# Board_2.net
KiCad netlist of a schematic drawn in EAGLE
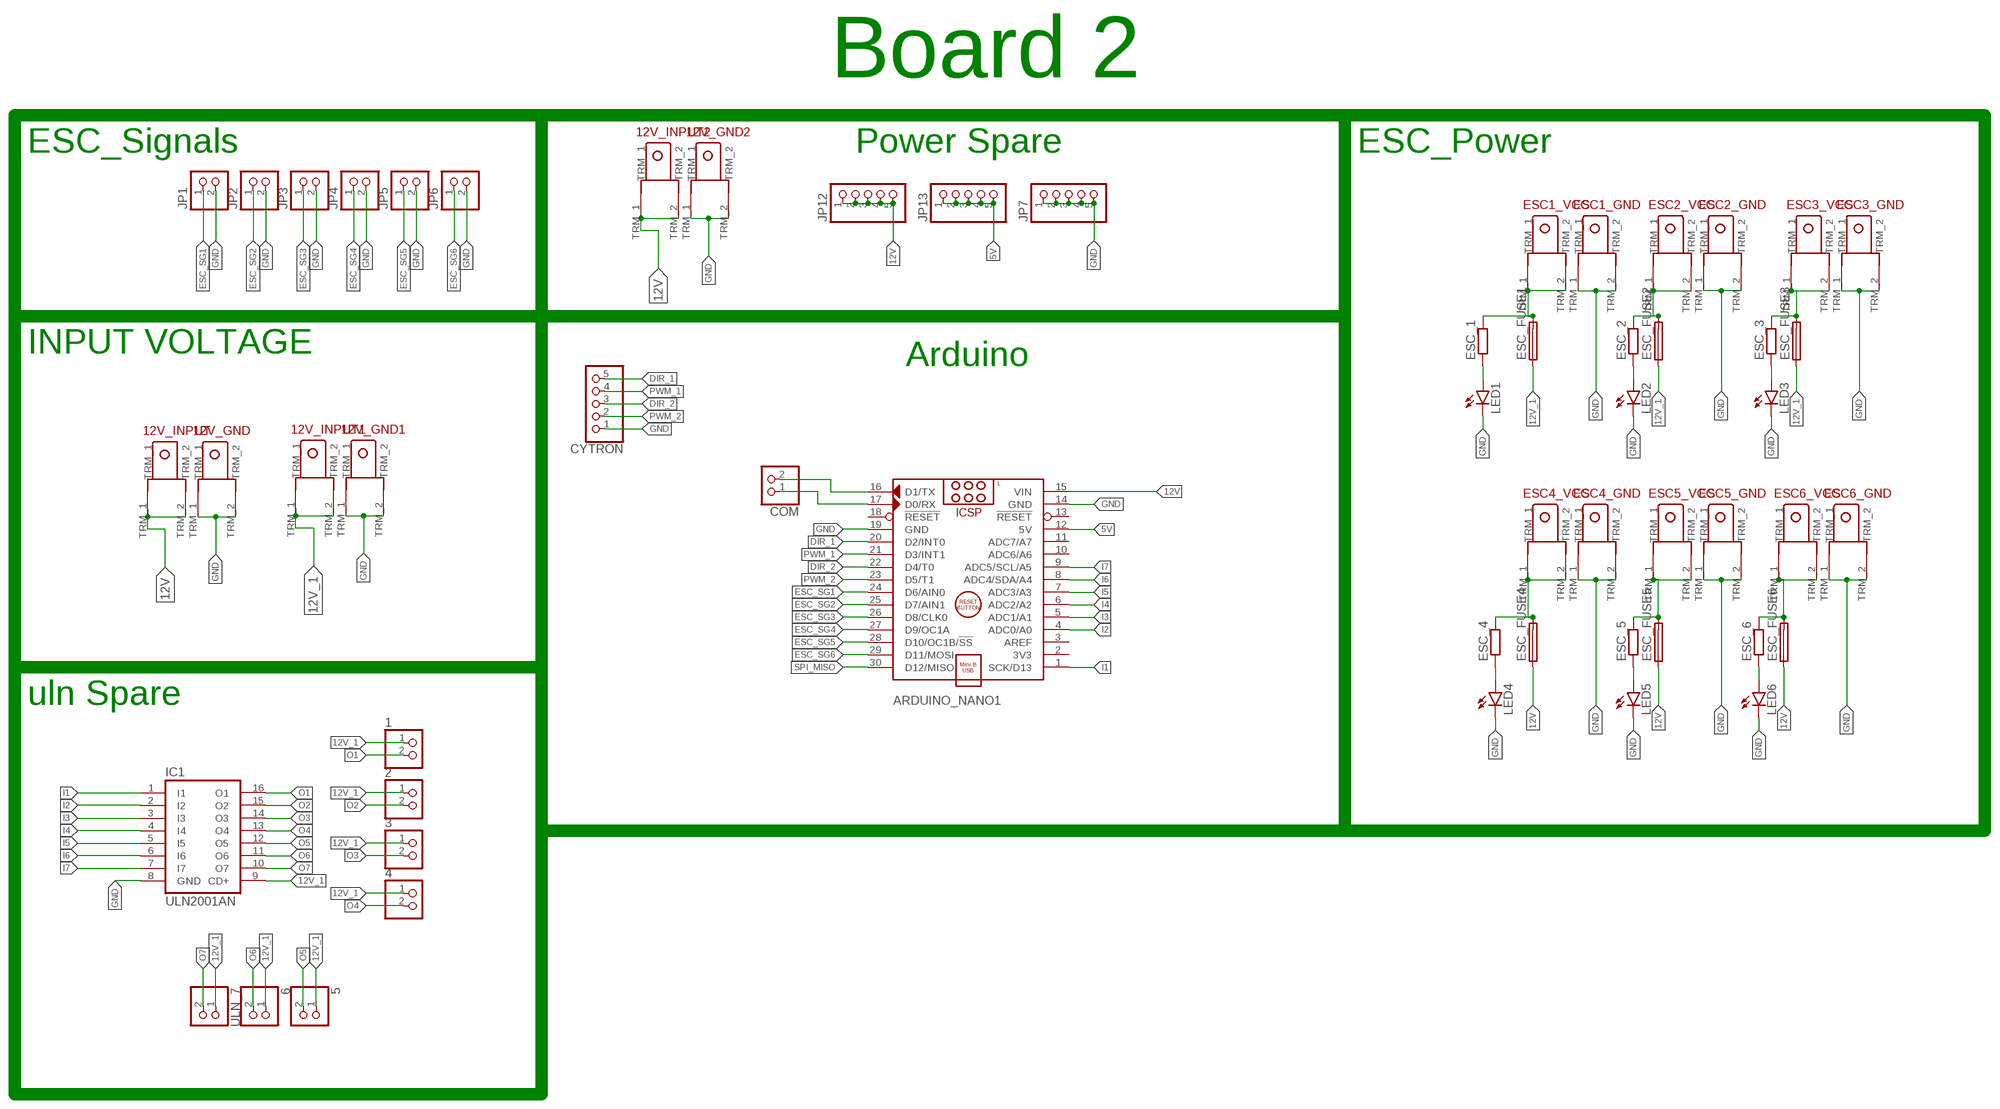
[diagram p0: schematic, sheet 1]

(export (version "E")
  (design (tool "Eeschema 10.0.6"))
  (components
    (comp (ref "1")
      (value "PINHD-1X2")
      (footprint "eagle-import:1X02")
      (libsource (lib "eagle-import") (part "PINHD-1X2"))
    )
    (comp (ref "2")
      (value "PINHD-1X2")
      (footprint "eagle-import:1X02")
      (libsource (lib "eagle-import") (part "PINHD-1X2"))
    )
    (comp (ref "3")
      (value "PINHD-1X2")
      (footprint "eagle-import:1X02")
      (libsource (lib "eagle-import") (part "PINHD-1X2"))
    )
    (comp (ref "4")
      (value "PINHD-1X2")
      (footprint "eagle-import:1X02")
      (libsource (lib "eagle-import") (part "PINHD-1X2"))
    )
    (comp (ref "5")
      (value "PINHD-1X2")
      (footprint "eagle-import:1X02")
      (libsource (lib "eagle-import") (part "PINHD-1X2"))
    )
    (comp (ref "6")
      (value "PINHD-1X2")
      (footprint "eagle-import:1X02")
      (libsource (lib "eagle-import") (part "PINHD-1X2"))
    )
    (comp (ref "12V_GND")
      (value "TERMINAL_EDITED")
      (footprint "eagle-import:TERMINAL_EDITED")
      (libsource (lib "eagle-import") (part "TERMINAL_EDITED"))
    )
    (comp (ref "12V_GND1")
      (value "TERMINAL_EDITED")
      (footprint "eagle-import:TERMINAL_EDITED")
      (libsource (lib "eagle-import") (part "TERMINAL_EDITED"))
    )
    (comp (ref "12V_GND2")
      (value "TERMINAL_EDITED")
      (footprint "eagle-import:TERMINAL_EDITED")
      (libsource (lib "eagle-import") (part "TERMINAL_EDITED"))
    )
    (comp (ref "12V_INPUT")
      (value "TERMINAL_EDITED")
      (footprint "eagle-import:TERMINAL_EDITED")
      (libsource (lib "eagle-import") (part "TERMINAL_EDITED"))
    )
    (comp (ref "12V_INPUT1")
      (value "TERMINAL_EDITED")
      (footprint "eagle-import:TERMINAL_EDITED")
      (libsource (lib "eagle-import") (part "TERMINAL_EDITED"))
    )
    (comp (ref "12V_INPUT2")
      (value "TERMINAL_EDITED")
      (footprint "eagle-import:TERMINAL_EDITED")
      (libsource (lib "eagle-import") (part "TERMINAL_EDITED"))
    )
    (comp (ref "ARDUINO_NANO1")
      (value "ARDUINO_NANO")
      (footprint "eagle-import:ARDUINO_NANO")
      (libsource (lib "eagle-import") (part "ARDUINO_NANO"))
    )
    (comp (ref "COM")
      (value "PINHD-1X2")
      (footprint "eagle-import:1X02")
      (libsource (lib "eagle-import") (part "PINHD-1X2"))
    )
    (comp (ref "CYTRON")
      (value "PINHD-1X5")
      (footprint "eagle-import:1X05")
      (libsource (lib "eagle-import") (part "PINHD-1X5"))
    )
    (comp (ref "ESC1_GND")
      (value "TERMINAL_EDITED")
      (footprint "eagle-import:TERMINAL_EDITED")
      (libsource (lib "eagle-import") (part "TERMINAL_EDITED"))
    )
    (comp (ref "ESC1_VCC")
      (value "TERMINAL_EDITED")
      (footprint "eagle-import:TERMINAL_EDITED")
      (libsource (lib "eagle-import") (part "TERMINAL_EDITED"))
    )
    (comp (ref "ESC2_GND")
      (value "TERMINAL_EDITED")
      (footprint "eagle-import:TERMINAL_EDITED")
      (libsource (lib "eagle-import") (part "TERMINAL_EDITED"))
    )
    (comp (ref "ESC2_VCC")
      (value "TERMINAL_EDITED")
      (footprint "eagle-import:TERMINAL_EDITED")
      (libsource (lib "eagle-import") (part "TERMINAL_EDITED"))
    )
    (comp (ref "ESC3_GND")
      (value "TERMINAL_EDITED")
      (footprint "eagle-import:TERMINAL_EDITED")
      (libsource (lib "eagle-import") (part "TERMINAL_EDITED"))
    )
    (comp (ref "ESC3_VCC")
      (value "TERMINAL_EDITED")
      (footprint "eagle-import:TERMINAL_EDITED")
      (libsource (lib "eagle-import") (part "TERMINAL_EDITED"))
    )
    (comp (ref "ESC4_GND")
      (value "TERMINAL_EDITED")
      (footprint "eagle-import:TERMINAL_EDITED")
      (libsource (lib "eagle-import") (part "TERMINAL_EDITED"))
    )
    (comp (ref "ESC4_VCC")
      (value "TERMINAL_EDITED")
      (footprint "eagle-import:TERMINAL_EDITED")
      (libsource (lib "eagle-import") (part "TERMINAL_EDITED"))
    )
    (comp (ref "ESC5_GND")
      (value "TERMINAL_EDITED")
      (footprint "eagle-import:TERMINAL_EDITED")
      (libsource (lib "eagle-import") (part "TERMINAL_EDITED"))
    )
    (comp (ref "ESC5_VCC")
      (value "TERMINAL_EDITED")
      (footprint "eagle-import:TERMINAL_EDITED")
      (libsource (lib "eagle-import") (part "TERMINAL_EDITED"))
    )
    (comp (ref "ESC6_GND")
      (value "TERMINAL_EDITED")
      (footprint "eagle-import:TERMINAL_EDITED")
      (libsource (lib "eagle-import") (part "TERMINAL_EDITED"))
    )
    (comp (ref "ESC6_VCC")
      (value "TERMINAL_EDITED")
      (footprint "eagle-import:TERMINAL_EDITED")
      (libsource (lib "eagle-import") (part "TERMINAL_EDITED"))
    )
    (comp (ref "ESC_1")
      (value "RESISTOR")
      (footprint "eagle-import:0207_10")
      (libsource (lib "eagle-import") (part "RESISTOR"))
    )
    (comp (ref "ESC_2")
      (value "RESISTOR")
      (footprint "eagle-import:0207_10")
      (libsource (lib "eagle-import") (part "RESISTOR"))
    )
    (comp (ref "ESC_3")
      (value "RESISTOR")
      (footprint "eagle-import:0207_10")
      (libsource (lib "eagle-import") (part "RESISTOR"))
    )
    (comp (ref "ESC_4")
      (value "RESISTOR")
      (footprint "eagle-import:0207_10")
      (libsource (lib "eagle-import") (part "RESISTOR"))
    )
    (comp (ref "ESC_5")
      (value "RESISTOR")
      (footprint "eagle-import:0207_10")
      (libsource (lib "eagle-import") (part "RESISTOR"))
    )
    (comp (ref "ESC_6")
      (value "RESISTOR")
      (footprint "eagle-import:0207_10")
      (libsource (lib "eagle-import") (part "RESISTOR"))
    )
    (comp (ref "ESC_FUSE1")
      (value "FUSE")
      (footprint "eagle-import:SH22,5A")
      (libsource (lib "eagle-import") (part "FUSE"))
    )
    (comp (ref "ESC_FUSE2")
      (value "FUSE")
      (footprint "eagle-import:SH22,5A")
      (libsource (lib "eagle-import") (part "FUSE"))
    )
    (comp (ref "ESC_FUSE3")
      (value "FUSE")
      (footprint "eagle-import:SH22,5A")
      (libsource (lib "eagle-import") (part "FUSE"))
    )
    (comp (ref "ESC_FUSE4")
      (value "FUSE")
      (footprint "eagle-import:SH22,5A")
      (libsource (lib "eagle-import") (part "FUSE"))
    )
    (comp (ref "ESC_FUSE5")
      (value "FUSE")
      (footprint "eagle-import:SH22,5A")
      (libsource (lib "eagle-import") (part "FUSE"))
    )
    (comp (ref "ESC_FUSE6")
      (value "FUSE")
      (footprint "eagle-import:SH22,5A")
      (libsource (lib "eagle-import") (part "FUSE"))
    )
    (comp (ref "IC1")
      (value "ULN2001AN")
      (footprint "eagle-import:DIL16")
      (libsource (lib "eagle-import") (part "ULN2001AN"))
    )
    (comp (ref "JP1")
      (value "PINHD-1X2")
      (footprint "eagle-import:1X02")
      (libsource (lib "eagle-import") (part "PINHD-1X2"))
    )
    (comp (ref "JP2")
      (value "PINHD-1X2")
      (footprint "eagle-import:1X02")
      (libsource (lib "eagle-import") (part "PINHD-1X2"))
    )
    (comp (ref "JP3")
      (value "PINHD-1X2")
      (footprint "eagle-import:1X02")
      (libsource (lib "eagle-import") (part "PINHD-1X2"))
    )
    (comp (ref "JP4")
      (value "PINHD-1X2")
      (footprint "eagle-import:1X02")
      (libsource (lib "eagle-import") (part "PINHD-1X2"))
    )
    (comp (ref "JP5")
      (value "PINHD-1X2")
      (footprint "eagle-import:1X02")
      (libsource (lib "eagle-import") (part "PINHD-1X2"))
    )
    (comp (ref "JP6")
      (value "PINHD-1X2")
      (footprint "eagle-import:1X02")
      (libsource (lib "eagle-import") (part "PINHD-1X2"))
    )
    (comp (ref "JP7")
      (value "PINHD-1X5")
      (footprint "eagle-import:1X05")
      (libsource (lib "eagle-import") (part "PINHD-1X5"))
    )
    (comp (ref "JP12")
      (value "PINHD-1X5")
      (footprint "eagle-import:1X05")
      (libsource (lib "eagle-import") (part "PINHD-1X5"))
    )
    (comp (ref "JP13")
      (value "PINHD-1X5")
      (footprint "eagle-import:1X05")
      (libsource (lib "eagle-import") (part "PINHD-1X5"))
    )
    (comp (ref "LED1")
      (value "LED5MM")
      (footprint "eagle-import:LED5MM")
      (libsource (lib "eagle-import") (part "LED5MM"))
    )
    (comp (ref "LED2")
      (value "LED5MM")
      (footprint "eagle-import:LED5MM")
      (libsource (lib "eagle-import") (part "LED5MM"))
    )
    (comp (ref "LED3")
      (value "LED5MM")
      (footprint "eagle-import:LED5MM")
      (libsource (lib "eagle-import") (part "LED5MM"))
    )
    (comp (ref "LED4")
      (value "LED5MM")
      (footprint "eagle-import:LED5MM")
      (libsource (lib "eagle-import") (part "LED5MM"))
    )
    (comp (ref "LED5")
      (value "LED5MM")
      (footprint "eagle-import:LED5MM")
      (libsource (lib "eagle-import") (part "LED5MM"))
    )
    (comp (ref "LED6")
      (value "LED5MM")
      (footprint "eagle-import:LED5MM")
      (libsource (lib "eagle-import") (part "LED5MM"))
    )
    (comp (ref "ULN_7")
      (value "PINHD-1X2")
      (footprint "eagle-import:1X02")
      (libsource (lib "eagle-import") (part "PINHD-1X2"))
    )
  )
  (nets
    (net (code "1") (name "5V") (class "Default")
      (node (ref "ARDUINO_NANO1") (pin "12") (pinfunction "5V_12") (pintype "power_in"))
      (node (ref "JP13") (pin "1") (pinfunction "1_1") (pintype "passive"))
      (node (ref "JP13") (pin "2") (pinfunction "2_2") (pintype "passive"))
      (node (ref "JP13") (pin "3") (pinfunction "3_3") (pintype "passive"))
      (node (ref "JP13") (pin "4") (pinfunction "4_4") (pintype "passive"))
      (node (ref "JP13") (pin "5") (pinfunction "5_5") (pintype "passive"))
    )
    (net (code "2") (name "12V") (class "Default")
      (node (ref "12V_INPUT") (pin "TRM_1") (pinfunction "TRM_1_TRM_1") (pintype "bidirectional"))
      (node (ref "12V_INPUT") (pin "TRM_2") (pinfunction "TRM_2_TRM_2") (pintype "bidirectional"))
      (node (ref "12V_INPUT2") (pin "TRM_1") (pinfunction "TRM_1_TRM_1") (pintype "bidirectional"))
      (node (ref "12V_INPUT2") (pin "TRM_2") (pinfunction "TRM_2_TRM_2") (pintype "bidirectional"))
      (node (ref "ARDUINO_NANO1") (pin "15") (pinfunction "VIN_15") (pintype "power_in"))
      (node (ref "ESC_FUSE4") (pin "1") (pinfunction "1_1") (pintype "passive"))
      (node (ref "ESC_FUSE5") (pin "1") (pinfunction "1_1") (pintype "passive"))
      (node (ref "ESC_FUSE6") (pin "1") (pinfunction "1_1") (pintype "passive"))
      (node (ref "JP12") (pin "1") (pinfunction "1_1") (pintype "passive"))
      (node (ref "JP12") (pin "2") (pinfunction "2_2") (pintype "passive"))
      (node (ref "JP12") (pin "3") (pinfunction "3_3") (pintype "passive"))
      (node (ref "JP12") (pin "4") (pinfunction "4_4") (pintype "passive"))
      (node (ref "JP12") (pin "5") (pinfunction "5_5") (pintype "passive"))
    )
    (net (code "3") (name "12V_1") (class "Default")
      (node (ref "1") (pin "1") (pinfunction "1_1") (pintype "passive"))
      (node (ref "12V_INPUT1") (pin "TRM_1") (pinfunction "TRM_1_TRM_1") (pintype "bidirectional"))
      (node (ref "12V_INPUT1") (pin "TRM_2") (pinfunction "TRM_2_TRM_2") (pintype "bidirectional"))
      (node (ref "2") (pin "1") (pinfunction "1_1") (pintype "passive"))
      (node (ref "3") (pin "1") (pinfunction "1_1") (pintype "passive"))
      (node (ref "4") (pin "1") (pinfunction "1_1") (pintype "passive"))
      (node (ref "5") (pin "1") (pinfunction "1_1") (pintype "passive"))
      (node (ref "6") (pin "1") (pinfunction "1_1") (pintype "passive"))
      (node (ref "ESC_FUSE1") (pin "1") (pinfunction "1_1") (pintype "passive"))
      (node (ref "ESC_FUSE2") (pin "1") (pinfunction "1_1") (pintype "passive"))
      (node (ref "ESC_FUSE3") (pin "1") (pinfunction "1_1") (pintype "passive"))
      (node (ref "IC1") (pin "9") (pinfunction "CD+_9") (pintype "passive"))
      (node (ref "ULN_7") (pin "1") (pinfunction "1_1") (pintype "passive"))
    )
    (net (code "4") (name "DIR_1") (class "Default")
      (node (ref "ARDUINO_NANO1") (pin "20") (pinfunction "D2/INT0_20") (pintype "bidirectional"))
      (node (ref "CYTRON") (pin "5") (pinfunction "5_5") (pintype "passive"))
    )
    (net (code "5") (name "DIR_2") (class "Default")
      (node (ref "ARDUINO_NANO1") (pin "22") (pinfunction "D4/T0_22") (pintype "bidirectional"))
      (node (ref "CYTRON") (pin "3") (pinfunction "3_3") (pintype "passive"))
    )
    (net (code "6") (name "ESC_SG1") (class "Default")
      (node (ref "ARDUINO_NANO1") (pin "24") (pinfunction "D6/AIN0_24") (pintype "bidirectional"))
      (node (ref "JP1") (pin "1") (pinfunction "1_1") (pintype "passive"))
    )
    (net (code "7") (name "ESC_SG2") (class "Default")
      (node (ref "ARDUINO_NANO1") (pin "25") (pinfunction "D7/AIN1_25") (pintype "bidirectional"))
      (node (ref "JP2") (pin "1") (pinfunction "1_1") (pintype "passive"))
    )
    (net (code "8") (name "ESC_SG3") (class "Default")
      (node (ref "ARDUINO_NANO1") (pin "26") (pinfunction "D8/CLK0_26") (pintype "bidirectional"))
      (node (ref "JP3") (pin "1") (pinfunction "1_1") (pintype "passive"))
    )
    (net (code "9") (name "ESC_SG4") (class "Default")
      (node (ref "ARDUINO_NANO1") (pin "27") (pinfunction "D9/OC1A_27") (pintype "bidirectional"))
      (node (ref "JP4") (pin "1") (pinfunction "1_1") (pintype "passive"))
    )
    (net (code "10") (name "ESC_SG5") (class "Default")
      (node (ref "ARDUINO_NANO1") (pin "28") (pinfunction "D10/OC1B/~{SS}_28") (pintype "bidirectional"))
      (node (ref "JP5") (pin "1") (pinfunction "1_1") (pintype "passive"))
    )
    (net (code "11") (name "ESC_SG6") (class "Default")
      (node (ref "ARDUINO_NANO1") (pin "29") (pinfunction "D11/MOSI_29") (pintype "bidirectional"))
      (node (ref "JP6") (pin "1") (pinfunction "1_1") (pintype "passive"))
    )
    (net (code "12") (name "GND") (class "Default")
      (node (ref "12V_GND") (pin "TRM_1") (pinfunction "TRM_1_TRM_1") (pintype "bidirectional"))
      (node (ref "12V_GND") (pin "TRM_2") (pinfunction "TRM_2_TRM_2") (pintype "bidirectional"))
      (node (ref "12V_GND1") (pin "TRM_1") (pinfunction "TRM_1_TRM_1") (pintype "bidirectional"))
      (node (ref "12V_GND1") (pin "TRM_2") (pinfunction "TRM_2_TRM_2") (pintype "bidirectional"))
      (node (ref "12V_GND2") (pin "TRM_1") (pinfunction "TRM_1_TRM_1") (pintype "bidirectional"))
      (node (ref "12V_GND2") (pin "TRM_2") (pinfunction "TRM_2_TRM_2") (pintype "bidirectional"))
      (node (ref "ARDUINO_NANO1") (pin "14") (pinfunction "GND_14") (pintype "power_in"))
      (node (ref "ARDUINO_NANO1") (pin "19") (pinfunction "GND_19") (pintype "power_in"))
      (node (ref "CYTRON") (pin "1") (pinfunction "1_1") (pintype "passive"))
      (node (ref "ESC1_GND") (pin "TRM_1") (pinfunction "TRM_1_TRM_1") (pintype "bidirectional"))
      (node (ref "ESC1_GND") (pin "TRM_2") (pinfunction "TRM_2_TRM_2") (pintype "bidirectional"))
      (node (ref "ESC2_GND") (pin "TRM_1") (pinfunction "TRM_1_TRM_1") (pintype "bidirectional"))
      (node (ref "ESC2_GND") (pin "TRM_2") (pinfunction "TRM_2_TRM_2") (pintype "bidirectional"))
      (node (ref "ESC3_GND") (pin "TRM_1") (pinfunction "TRM_1_TRM_1") (pintype "bidirectional"))
      (node (ref "ESC3_GND") (pin "TRM_2") (pinfunction "TRM_2_TRM_2") (pintype "bidirectional"))
      (node (ref "ESC4_GND") (pin "TRM_1") (pinfunction "TRM_1_TRM_1") (pintype "bidirectional"))
      (node (ref "ESC4_GND") (pin "TRM_2") (pinfunction "TRM_2_TRM_2") (pintype "bidirectional"))
      (node (ref "ESC5_GND") (pin "TRM_1") (pinfunction "TRM_1_TRM_1") (pintype "bidirectional"))
      (node (ref "ESC5_GND") (pin "TRM_2") (pinfunction "TRM_2_TRM_2") (pintype "bidirectional"))
      (node (ref "ESC6_GND") (pin "TRM_1") (pinfunction "TRM_1_TRM_1") (pintype "bidirectional"))
      (node (ref "ESC6_GND") (pin "TRM_2") (pinfunction "TRM_2_TRM_2") (pintype "bidirectional"))
      (node (ref "IC1") (pin "8") (pinfunction "GND_8") (pintype "power_in"))
      (node (ref "JP1") (pin "2") (pinfunction "2_2") (pintype "passive"))
      (node (ref "JP2") (pin "2") (pinfunction "2_2") (pintype "passive"))
      (node (ref "JP3") (pin "2") (pinfunction "2_2") (pintype "passive"))
      (node (ref "JP4") (pin "2") (pinfunction "2_2") (pintype "passive"))
      (node (ref "JP5") (pin "2") (pinfunction "2_2") (pintype "passive"))
      (node (ref "JP6") (pin "2") (pinfunction "2_2") (pintype "passive"))
      (node (ref "JP7") (pin "1") (pinfunction "1_1") (pintype "passive"))
      (node (ref "JP7") (pin "2") (pinfunction "2_2") (pintype "passive"))
      (node (ref "JP7") (pin "3") (pinfunction "3_3") (pintype "passive"))
      (node (ref "JP7") (pin "4") (pinfunction "4_4") (pintype "passive"))
      (node (ref "JP7") (pin "5") (pinfunction "5_5") (pintype "passive"))
      (node (ref "LED1") (pin "K") (pinfunction "C_K") (pintype "passive"))
      (node (ref "LED2") (pin "K") (pinfunction "C_K") (pintype "passive"))
      (node (ref "LED3") (pin "K") (pinfunction "C_K") (pintype "passive"))
      (node (ref "LED4") (pin "K") (pinfunction "C_K") (pintype "passive"))
      (node (ref "LED5") (pin "K") (pinfunction "C_K") (pintype "passive"))
      (node (ref "LED6") (pin "K") (pinfunction "C_K") (pintype "passive"))
    )
    (net (code "13") (name "I1") (class "Default")
      (node (ref "ARDUINO_NANO1") (pin "1") (pinfunction "SCK/D13_1") (pintype "bidirectional"))
      (node (ref "IC1") (pin "1") (pinfunction "I1_1") (pintype "input"))
    )
    (net (code "14") (name "I2") (class "Default")
      (node (ref "ARDUINO_NANO1") (pin "4") (pinfunction "ADC0/A0_4") (pintype "bidirectional"))
      (node (ref "IC1") (pin "2") (pinfunction "I2_2") (pintype "input"))
    )
    (net (code "15") (name "I3") (class "Default")
      (node (ref "ARDUINO_NANO1") (pin "5") (pinfunction "ADC1/A1_5") (pintype "bidirectional"))
      (node (ref "IC1") (pin "3") (pinfunction "I3_3") (pintype "input"))
    )
    (net (code "16") (name "I4") (class "Default")
      (node (ref "ARDUINO_NANO1") (pin "6") (pinfunction "ADC2/A2_6") (pintype "bidirectional"))
      (node (ref "IC1") (pin "4") (pinfunction "I4_4") (pintype "input"))
    )
    (net (code "17") (name "I5") (class "Default")
      (node (ref "ARDUINO_NANO1") (pin "7") (pinfunction "ADC3/A3_7") (pintype "bidirectional"))
      (node (ref "IC1") (pin "5") (pinfunction "I5_5") (pintype "input"))
    )
    (net (code "18") (name "I6") (class "Default")
      (node (ref "ARDUINO_NANO1") (pin "8") (pinfunction "ADC4/SDA/A4_8") (pintype "bidirectional"))
      (node (ref "IC1") (pin "6") (pinfunction "I6_6") (pintype "input"))
    )
    (net (code "19") (name "I7") (class "Default")
      (node (ref "ARDUINO_NANO1") (pin "9") (pinfunction "ADC5/SCL/A5_9") (pintype "bidirectional"))
      (node (ref "IC1") (pin "7") (pinfunction "I7_7") (pintype "input"))
    )
    (net (code "20") (name "Net-(ARDUINO_NANO1-D0{slash}RX)") (class "Default")
      (node (ref "ARDUINO_NANO1") (pin "17") (pinfunction "D0/RX_17") (pintype "bidirectional"))
      (node (ref "COM") (pin "1") (pinfunction "1_1") (pintype "passive"))
    )
    (net (code "21") (name "Net-(ARDUINO_NANO1-D1{slash}TX)") (class "Default")
      (node (ref "ARDUINO_NANO1") (pin "16") (pinfunction "D1/TX_16") (pintype "bidirectional"))
      (node (ref "COM") (pin "2") (pinfunction "2_2") (pintype "passive"))
    )
    (net (code "22") (name "Net-(ESC1_VCC-PadTRM_1)") (class "Default")
      (node (ref "ESC1_VCC") (pin "TRM_1") (pinfunction "TRM_1_TRM_1") (pintype "bidirectional"))
      (node (ref "ESC1_VCC") (pin "TRM_2") (pinfunction "TRM_2_TRM_2") (pintype "bidirectional"))
      (node (ref "ESC_1") (pin "2") (pinfunction "2_2") (pintype "passive"))
      (node (ref "ESC_FUSE1") (pin "2") (pinfunction "2_2") (pintype "passive"))
    )
    (net (code "23") (name "Net-(ESC2_VCC-PadTRM_1)") (class "Default")
      (node (ref "ESC2_VCC") (pin "TRM_1") (pinfunction "TRM_1_TRM_1") (pintype "bidirectional"))
      (node (ref "ESC2_VCC") (pin "TRM_2") (pinfunction "TRM_2_TRM_2") (pintype "bidirectional"))
      (node (ref "ESC_2") (pin "2") (pinfunction "2_2") (pintype "passive"))
      (node (ref "ESC_FUSE2") (pin "2") (pinfunction "2_2") (pintype "passive"))
    )
    (net (code "24") (name "Net-(ESC3_VCC-PadTRM_1)") (class "Default")
      (node (ref "ESC3_VCC") (pin "TRM_1") (pinfunction "TRM_1_TRM_1") (pintype "bidirectional"))
      (node (ref "ESC3_VCC") (pin "TRM_2") (pinfunction "TRM_2_TRM_2") (pintype "bidirectional"))
      (node (ref "ESC_3") (pin "2") (pinfunction "2_2") (pintype "passive"))
      (node (ref "ESC_FUSE3") (pin "2") (pinfunction "2_2") (pintype "passive"))
    )
    (net (code "25") (name "Net-(ESC4_VCC-PadTRM_1)") (class "Default")
      (node (ref "ESC4_VCC") (pin "TRM_1") (pinfunction "TRM_1_TRM_1") (pintype "bidirectional"))
      (node (ref "ESC4_VCC") (pin "TRM_2") (pinfunction "TRM_2_TRM_2") (pintype "bidirectional"))
      (node (ref "ESC_4") (pin "2") (pinfunction "2_2") (pintype "passive"))
      (node (ref "ESC_FUSE4") (pin "2") (pinfunction "2_2") (pintype "passive"))
    )
    (net (code "26") (name "Net-(ESC5_VCC-PadTRM_1)") (class "Default")
      (node (ref "ESC5_VCC") (pin "TRM_1") (pinfunction "TRM_1_TRM_1") (pintype "bidirectional"))
      (node (ref "ESC5_VCC") (pin "TRM_2") (pinfunction "TRM_2_TRM_2") (pintype "bidirectional"))
      (node (ref "ESC_5") (pin "2") (pinfunction "2_2") (pintype "passive"))
      (node (ref "ESC_FUSE5") (pin "2") (pinfunction "2_2") (pintype "passive"))
    )
    (net (code "27") (name "Net-(ESC6_VCC-PadTRM_1)") (class "Default")
      (node (ref "ESC6_VCC") (pin "TRM_1") (pinfunction "TRM_1_TRM_1") (pintype "bidirectional"))
      (node (ref "ESC6_VCC") (pin "TRM_2") (pinfunction "TRM_2_TRM_2") (pintype "bidirectional"))
      (node (ref "ESC_6") (pin "2") (pinfunction "2_2") (pintype "passive"))
      (node (ref "ESC_FUSE6") (pin "2") (pinfunction "2_2") (pintype "passive"))
    )
    (net (code "28") (name "Net-(ESC_1-Pad1)") (class "Default")
      (node (ref "ESC_1") (pin "1") (pinfunction "1_1") (pintype "passive"))
      (node (ref "LED1") (pin "A") (pinfunction "A_A") (pintype "passive"))
    )
    (net (code "29") (name "Net-(ESC_2-Pad1)") (class "Default")
      (node (ref "ESC_2") (pin "1") (pinfunction "1_1") (pintype "passive"))
      (node (ref "LED2") (pin "A") (pinfunction "A_A") (pintype "passive"))
    )
    (net (code "30") (name "Net-(ESC_3-Pad1)") (class "Default")
      (node (ref "ESC_3") (pin "1") (pinfunction "1_1") (pintype "passive"))
      (node (ref "LED3") (pin "A") (pinfunction "A_A") (pintype "passive"))
    )
    (net (code "31") (name "Net-(ESC_4-Pad1)") (class "Default")
      (node (ref "ESC_4") (pin "1") (pinfunction "1_1") (pintype "passive"))
      (node (ref "LED4") (pin "A") (pinfunction "A_A") (pintype "passive"))
    )
    (net (code "32") (name "Net-(ESC_5-Pad1)") (class "Default")
      (node (ref "ESC_5") (pin "1") (pinfunction "1_1") (pintype "passive"))
      (node (ref "LED5") (pin "A") (pinfunction "A_A") (pintype "passive"))
    )
    (net (code "33") (name "Net-(ESC_6-Pad1)") (class "Default")
      (node (ref "ESC_6") (pin "1") (pinfunction "1_1") (pintype "passive"))
      (node (ref "LED6") (pin "A") (pinfunction "A_A") (pintype "passive"))
    )
    (net (code "34") (name "O1") (class "Default")
      (node (ref "1") (pin "2") (pinfunction "2_2") (pintype "passive"))
      (node (ref "IC1") (pin "16") (pinfunction "O1_16") (pintype "open_collector"))
    )
    (net (code "35") (name "O2") (class "Default")
      (node (ref "2") (pin "2") (pinfunction "2_2") (pintype "passive"))
      (node (ref "IC1") (pin "15") (pinfunction "O2_15") (pintype "open_collector"))
    )
    (net (code "36") (name "O3") (class "Default")
      (node (ref "3") (pin "2") (pinfunction "2_2") (pintype "passive"))
      (node (ref "IC1") (pin "14") (pinfunction "O3_14") (pintype "open_collector"))
    )
    (net (code "37") (name "O4") (class "Default")
      (node (ref "4") (pin "2") (pinfunction "2_2") (pintype "passive"))
      (node (ref "IC1") (pin "13") (pinfunction "O4_13") (pintype "open_collector"))
    )
    (net (code "38") (name "O5") (class "Default")
      (node (ref "5") (pin "2") (pinfunction "2_2") (pintype "passive"))
      (node (ref "IC1") (pin "12") (pinfunction "O5_12") (pintype "open_collector"))
    )
    (net (code "39") (name "O6") (class "Default")
      (node (ref "6") (pin "2") (pinfunction "2_2") (pintype "passive"))
      (node (ref "IC1") (pin "11") (pinfunction "O6_11") (pintype "open_collector"))
    )
    (net (code "40") (name "O7") (class "Default")
      (node (ref "IC1") (pin "10") (pinfunction "O7_10") (pintype "open_collector"))
      (node (ref "ULN_7") (pin "2") (pinfunction "2_2") (pintype "passive"))
    )
    (net (code "41") (name "PWM_1") (class "Default")
      (node (ref "ARDUINO_NANO1") (pin "21") (pinfunction "D3/INT1_21") (pintype "bidirectional"))
      (node (ref "CYTRON") (pin "4") (pinfunction "4_4") (pintype "passive"))
    )
    (net (code "42") (name "PWM_2") (class "Default")
      (node (ref "ARDUINO_NANO1") (pin "23") (pinfunction "D5/T1_23") (pintype "bidirectional"))
      (node (ref "CYTRON") (pin "2") (pinfunction "2_2") (pintype "passive"))
    )
    (net (code "43") (name "SPI_MISO") (class "Default")
      (node (ref "ARDUINO_NANO1") (pin "30") (pinfunction "D12/MISO_30") (pintype "bidirectional"))
    )
    (net (code "44") (name "unconnected-(ARDUINO_NANO1-3V3-Pad2)") (class "Default")
      (node (ref "ARDUINO_NANO1") (pin "2") (pinfunction "3V3_2") (pintype "output"))
    )
    (net (code "45") (name "unconnected-(ARDUINO_NANO1-ADC6{slash}A6-Pad10)") (class "Default")
      (node (ref "ARDUINO_NANO1") (pin "10") (pinfunction "ADC6/A6_10") (pintype "bidirectional"))
    )
    (net (code "46") (name "unconnected-(ARDUINO_NANO1-ADC7{slash}A7-Pad11)") (class "Default")
      (node (ref "ARDUINO_NANO1") (pin "11") (pinfunction "ADC7/A7_11") (pintype "bidirectional"))
    )
    (net (code "47") (name "unconnected-(ARDUINO_NANO1-AREF-Pad3)") (class "Default")
      (node (ref "ARDUINO_NANO1") (pin "3") (pinfunction "AREF_3") (pintype "input"))
    )
    (net (code "48") (name "unconnected-(ARDUINO_NANO1-~{RESET}-Pad13)") (class "Default")
      (node (ref "ARDUINO_NANO1") (pin "13") (pinfunction "~{RESET}_13") (pintype "input"))
    )
    (net (code "49") (name "unconnected-(ARDUINO_NANO1-~{RESET}-Pad18)") (class "Default")
      (node (ref "ARDUINO_NANO1") (pin "18") (pinfunction "~{RESET}_18") (pintype "input"))
    )
  )
)
